# Sheet2.net
KiCad netlist of a schematic drawn in Altium Designer
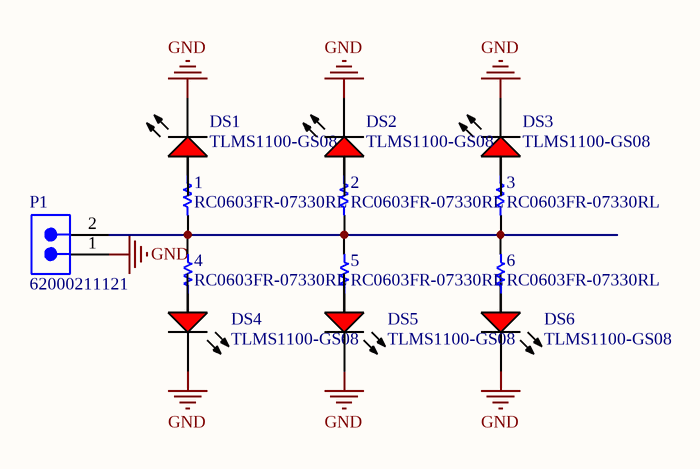
[diagram p0: Sheet2.SchDoc]

(export (version "E")
  (design (tool "Eeschema 10.0.6"))
  (components
    (comp (ref "1")
      (value "RC0603FR-07330RL")
      (footprint "RESC1608X55X25NL10T15")
      (description "Chip Resistor, 330 Ohm, +/- 1%, 0.1 W, -55 to 155 degC, 0603 (1608 Metric), RoHS, Tape and Reel")
      (fields (field (name "TOLERANCE") "10%"))
      (libsource (lib "Altium Content Vault") (part "RES-2"))
    )
    (comp (ref "2")
      (value "RC0603FR-07330RL")
      (footprint "RESC1608X55X25NL10T15")
      (description "Chip Resistor, 330 Ohm, +/- 1%, 0.1 W, -55 to 155 degC, 0603 (1608 Metric), RoHS, Tape and Reel")
      (fields (field (name "TOLERANCE") "10%"))
      (libsource (lib "Altium Content Vault") (part "RES-2"))
    )
    (comp (ref "3")
      (value "RC0603FR-07330RL")
      (footprint "RESC1608X55X25NL10T15")
      (description "Chip Resistor, 330 Ohm, +/- 1%, 0.1 W, -55 to 155 degC, 0603 (1608 Metric), RoHS, Tape and Reel")
      (fields (field (name "TOLERANCE") "10%"))
      (libsource (lib "Altium Content Vault") (part "RES-2"))
    )
    (comp (ref "4")
      (value "RC0603FR-07330RL")
      (footprint "RESC1608X55X25NL10T15")
      (description "Chip Resistor, 330 Ohm, +/- 1%, 0.1 W, -55 to 155 degC, 0603 (1608 Metric), RoHS, Tape and Reel")
      (fields (field (name "TOLERANCE") "10%"))
      (libsource (lib "Altium Content Vault") (part "RES-2"))
    )
    (comp (ref "5")
      (value "RC0603FR-07330RL")
      (footprint "RESC1608X55X25NL10T15")
      (description "Chip Resistor, 330 Ohm, +/- 1%, 0.1 W, -55 to 155 degC, 0603 (1608 Metric), RoHS, Tape and Reel")
      (fields (field (name "TOLERANCE") "10%"))
      (libsource (lib "Altium Content Vault") (part "RES-2"))
    )
    (comp (ref "6")
      (value "RC0603FR-07330RL")
      (footprint "RESC1608X55X25NL10T15")
      (description "Chip Resistor, 330 Ohm, +/- 1%, 0.1 W, -55 to 155 degC, 0603 (1608 Metric), RoHS, Tape and Reel")
      (fields (field (name "TOLERANCE") "10%"))
      (libsource (lib "Altium Content Vault") (part "RES-2"))
    )
    (comp (ref "DS1")
      (value "TLMS1100-GS08")
      (footprint "VISH-TLMX1100_V")
      (description "LED, RED, 2.1 V, -40 to 100 degC, 2-Pin SMD (0603), RoHS, Tape and Reel")
      (fields (field (name "TOLERANCE") "5%"))
      (libsource (lib "Altium Content Vault") (part "LED-RED-AK-2"))
    )
    (comp (ref "DS2")
      (value "TLMS1100-GS08")
      (footprint "VISH-TLMX1100_V")
      (description "LED, RED, 2.1 V, -40 to 100 degC, 2-Pin SMD (0603), RoHS, Tape and Reel")
      (fields (field (name "TOLERANCE") "5%"))
      (libsource (lib "Altium Content Vault") (part "LED-RED-AK-2"))
    )
    (comp (ref "DS3")
      (value "TLMS1100-GS08")
      (footprint "VISH-TLMX1100_V")
      (description "LED, RED, 2.1 V, -40 to 100 degC, 2-Pin SMD (0603), RoHS, Tape and Reel")
      (fields (field (name "TOLERANCE") "5%"))
      (libsource (lib "Altium Content Vault") (part "LED-RED-AK-2"))
    )
    (comp (ref "DS4")
      (value "TLMS1100-GS08")
      (footprint "VISH-TLMX1100_V")
      (description "LED, RED, 2.1 V, -40 to 100 degC, 2-Pin SMD (0603), RoHS, Tape and Reel")
      (fields (field (name "TOLERANCE") "5%"))
      (libsource (lib "Altium Content Vault") (part "LED-RED-AK-2"))
    )
    (comp (ref "DS5")
      (value "TLMS1100-GS08")
      (footprint "VISH-TLMX1100_V")
      (description "LED, RED, 2.1 V, -40 to 100 degC, 2-Pin SMD (0603), RoHS, Tape and Reel")
      (fields (field (name "TOLERANCE") "5%"))
      (libsource (lib "Altium Content Vault") (part "LED-RED-AK-2"))
    )
    (comp (ref "DS6")
      (value "TLMS1100-GS08")
      (footprint "VISH-TLMX1100_V")
      (description "LED, RED, 2.1 V, -40 to 100 degC, 2-Pin SMD (0603), RoHS, Tape and Reel")
      (fields (field (name "TOLERANCE") "5%"))
      (libsource (lib "Altium Content Vault") (part "LED-RED-AK-2"))
    )
    (comp (ref "P1")
      (value "62000211121")
      (footprint "62000211121")
      (libsource (lib "Altium Content Vault") (part "Header_Male_1R_02P"))
    )
  )
  (nets
    (net (code "1") (name "GND") (class "Default")
      (node (ref "DS1") (pin "2") (pinfunction "K_2") (pintype "passive"))
      (node (ref "DS2") (pin "2") (pinfunction "K_2") (pintype "passive"))
      (node (ref "DS3") (pin "2") (pinfunction "K_2") (pintype "passive"))
      (node (ref "DS4") (pin "2") (pinfunction "K_2") (pintype "passive"))
      (node (ref "DS5") (pin "2") (pinfunction "K_2") (pintype "passive"))
      (node (ref "DS6") (pin "2") (pinfunction "K_2") (pintype "passive"))
      (node (ref "P1") (pin "1") (pinfunction "1_1") (pintype "passive"))
    )
    (net (code "2") (name "Net-(1-Pad2)") (class "Default")
      (node (ref "1") (pin "2") (pinfunction "2_2") (pintype "passive"))
      (node (ref "2") (pin "2") (pinfunction "2_2") (pintype "passive"))
      (node (ref "3") (pin "2") (pinfunction "2_2") (pintype "passive"))
      (node (ref "4") (pin "2") (pinfunction "2_2") (pintype "passive"))
      (node (ref "5") (pin "2") (pinfunction "2_2") (pintype "passive"))
      (node (ref "6") (pin "2") (pinfunction "2_2") (pintype "passive"))
      (node (ref "P1") (pin "2") (pinfunction "2_2") (pintype "passive"))
    )
    (net (code "3") (name "unconnected-(1-Pad1)") (class "Default")
      (node (ref "1") (pin "1") (pinfunction "1_1") (pintype "passive"))
    )
    (net (code "4") (name "unconnected-(2-Pad1)") (class "Default")
      (node (ref "2") (pin "1") (pinfunction "1_1") (pintype "passive"))
    )
    (net (code "5") (name "unconnected-(3-Pad1)") (class "Default")
      (node (ref "3") (pin "1") (pinfunction "1_1") (pintype "passive"))
    )
    (net (code "6") (name "unconnected-(4-Pad1)") (class "Default")
      (node (ref "4") (pin "1") (pinfunction "1_1") (pintype "passive"))
    )
    (net (code "7") (name "unconnected-(5-Pad1)") (class "Default")
      (node (ref "5") (pin "1") (pinfunction "1_1") (pintype "passive"))
    )
    (net (code "8") (name "unconnected-(6-Pad1)") (class "Default")
      (node (ref "6") (pin "1") (pinfunction "1_1") (pintype "passive"))
    )
    (net (code "9") (name "unconnected-(DS1-A-Pad1)") (class "Default")
      (node (ref "DS1") (pin "1") (pinfunction "A_1") (pintype "passive"))
    )
    (net (code "10") (name "unconnected-(DS2-A-Pad1)") (class "Default")
      (node (ref "DS2") (pin "1") (pinfunction "A_1") (pintype "passive"))
    )
    (net (code "11") (name "unconnected-(DS3-A-Pad1)") (class "Default")
      (node (ref "DS3") (pin "1") (pinfunction "A_1") (pintype "passive"))
    )
    (net (code "12") (name "unconnected-(DS4-A-Pad1)") (class "Default")
      (node (ref "DS4") (pin "1") (pinfunction "A_1") (pintype "passive"))
    )
    (net (code "13") (name "unconnected-(DS5-A-Pad1)") (class "Default")
      (node (ref "DS5") (pin "1") (pinfunction "A_1") (pintype "passive"))
    )
    (net (code "14") (name "unconnected-(DS6-A-Pad1)") (class "Default")
      (node (ref "DS6") (pin "1") (pinfunction "A_1") (pintype "passive"))
    )
  )
)
